# DoubleSwitch.net
KiCad netlist of a schematic drawn in EAGLE
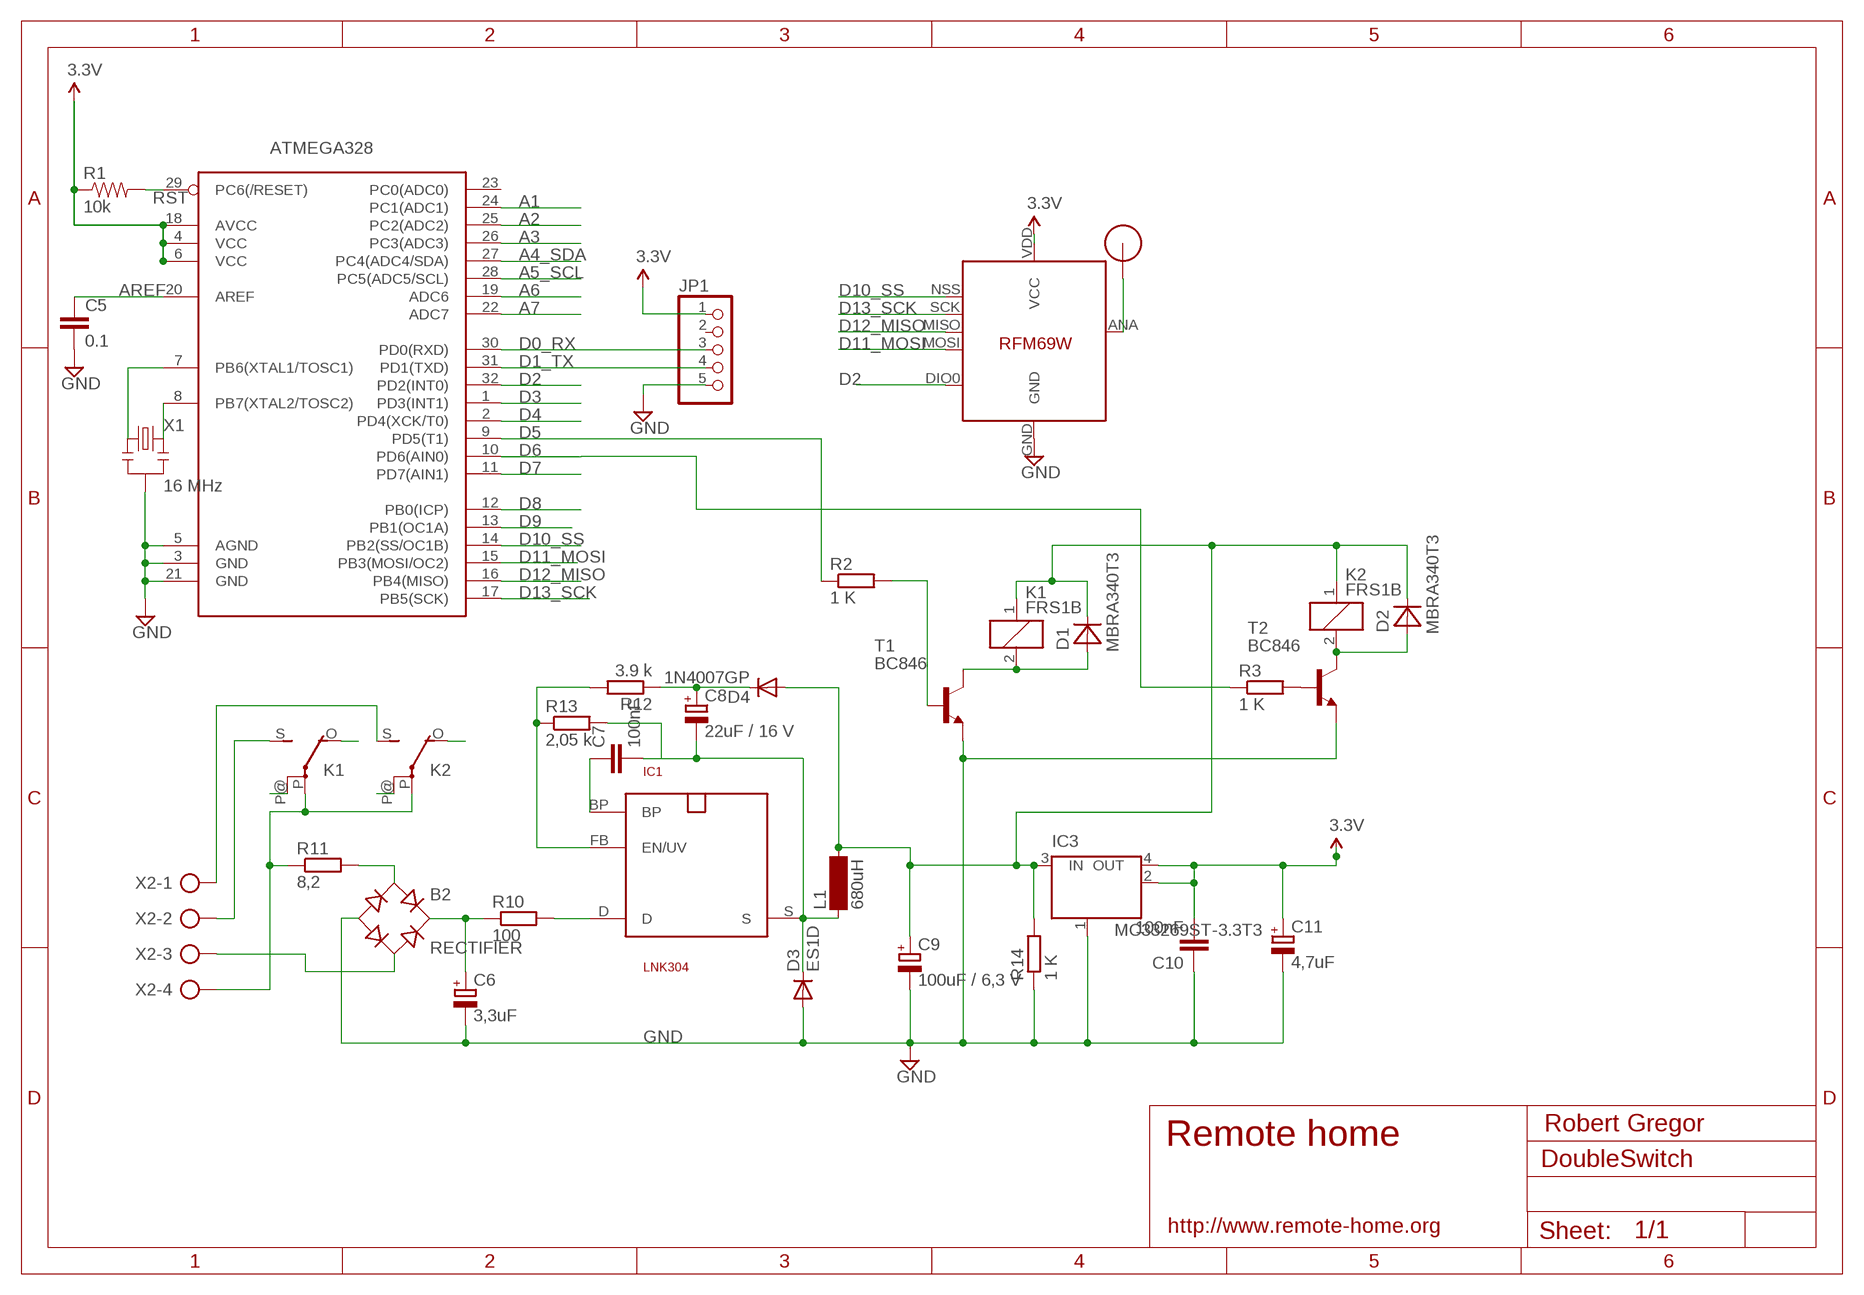
[diagram p0: schematic, sheet 1]

(export (version "E")
  (design (tool "Eeschema 10.0.6"))
  (components
    (comp (ref "ATMEGA328")
      (value "ATMega-328")
      (footprint "eagle-import:TQFP32-08")
      (libsource (lib "eagle-import") (part "ATMEGA168/328TQFP32"))
    )
    (comp (ref "B2")
      (value "RECTIFIER")
      (footprint "eagle-import:TO-269AA")
      (libsource (lib "eagle-import") (part "RECTIFIER-S40"))
    )
    (comp (ref "C5")
      (value "0.1")
      (footprint "eagle-import:0603-CAP")
      (libsource (lib "eagle-import") (part "CAP0603-CAP"))
    )
    (comp (ref "C6")
      (value "3,3uF")
      (footprint "eagle-import:E5-10,5")
      (libsource (lib "eagle-import") (part "CPOL-EUE5-10.5"))
    )
    (comp (ref "C7")
      (value "100nF")
      (footprint "eagle-import:C2012")
      (libsource (lib "eagle-import") (part "C-EUC2012"))
    )
    (comp (ref "C8")
      (value "22uF / 16 V")
      (footprint "eagle-import:SMC_C")
      (libsource (lib "eagle-import") (part "CPOL-EUSMCC"))
    )
    (comp (ref "C9")
      (value "100uF / 6,3 V")
      (footprint "eagle-import:E2,5-5")
      (libsource (lib "eagle-import") (part "CPOL-EUE2.5-5"))
    )
    (comp (ref "C10")
      (value "100nF")
      (footprint "eagle-import:C2012")
      (libsource (lib "eagle-import") (part "C-EUC2012"))
    )
    (comp (ref "C11")
      (value "4,7uF")
      (footprint "eagle-import:SMC_A")
      (libsource (lib "eagle-import") (part "CPOL-EUSMCA"))
    )
    (comp (ref "D1")
      (value "MBRA340T3")
      (footprint "eagle-import:SMA")
      (libsource (lib "eagle-import") (part "MBRA340T3"))
    )
    (comp (ref "D2")
      (value "MBRA340T3")
      (footprint "eagle-import:SMA")
      (libsource (lib "eagle-import") (part "MBRA340T3"))
    )
    (comp (ref "D3")
      (value "ES1D")
      (footprint "eagle-import:DO214AC")
      (libsource (lib "eagle-import") (part "DIODE-DO214AC"))
    )
    (comp (ref "D4")
      (value "1N4007GP")
      (footprint "eagle-import:DO214AA")
      (libsource (lib "eagle-import") (part "DIODE-DO214AA"))
    )
    (comp (ref "IC1")
      (value "LNK304")
      (footprint "eagle-import:SO-8C")
      (libsource (lib "eagle-import") (part "SO-8C"))
    )
    (comp (ref "IC3")
      (value "MC33269ST-3.3T3")
      (footprint "eagle-import:SOT223")
      (libsource (lib "eagle-import") (part "MC33269ST-3.3T3"))
    )
    (comp (ref "JP1")
      (value "PINHD-1X5")
      (footprint "eagle-import:1X05")
      (libsource (lib "eagle-import") (part "PINHD-1X5"))
    )
    (comp (ref "K1")
      (value "FRS1B")
      (footprint "eagle-import:FRS1B")
      (libsource (lib "eagle-import") (part "FRS1B"))
    )
    (comp (ref "K2")
      (value "FRS1B")
      (footprint "eagle-import:FRS1B")
      (libsource (lib "eagle-import") (part "FRS1B"))
    )
    (comp (ref "L1")
      (value "680uH")
      (footprint "eagle-import:BS11")
      (libsource (lib "eagle-import") (part "BS11"))
    )
    (comp (ref "R1")
      (value "10k")
      (footprint "eagle-import:0603-RES")
      (libsource (lib "eagle-import") (part "RESISTOR0603-RES"))
    )
    (comp (ref "R2")
      (value "1 K")
      (footprint "eagle-import:M2012")
      (libsource (lib "eagle-import") (part "R-EU_M2012"))
    )
    (comp (ref "R3")
      (value "1 K")
      (footprint "eagle-import:M2012")
      (libsource (lib "eagle-import") (part "R-EU_M2012"))
    )
    (comp (ref "R10")
      (value "100")
      (footprint "eagle-import:R2512W")
      (libsource (lib "eagle-import") (part "R-EU_R2512W"))
    )
    (comp (ref "R11")
      (value "8,2")
      (footprint "eagle-import:0411_12")
      (libsource (lib "eagle-import") (part "R-EU_0411/12"))
    )
    (comp (ref "R12")
      (value "3.9 k")
      (footprint "eagle-import:M2012")
      (libsource (lib "eagle-import") (part "R-EU_M2012"))
    )
    (comp (ref "R13")
      (value "2,05 k")
      (footprint "eagle-import:M2012")
      (libsource (lib "eagle-import") (part "R-EU_M2012"))
    )
    (comp (ref "R14")
      (value "1 K")
      (footprint "eagle-import:M2012")
      (libsource (lib "eagle-import") (part "R-EU_M2012"))
    )
    (comp (ref "T1")
      (value "BC846")
      (footprint "eagle-import:SOT23")
      (libsource (lib "eagle-import") (part "BC846"))
    )
    (comp (ref "T2")
      (value "BC846")
      (footprint "eagle-import:SOT23")
      (libsource (lib "eagle-import") (part "BC846"))
    )
    (comp (ref "U$1")
      (value "RFM12B_ANTENNA")
      (footprint "eagle-import:RFM12B-ANTENNA")
      (libsource (lib "eagle-import") (part "RFM12B_ANTENNA"))
    )
    (comp (ref "U$5")
      (value "RFM69")
      (footprint "eagle-import:RFM69W-MINPADS")
      (libsource (lib "eagle-import") (part "RFM69"))
    )
    (comp (ref "X1")
      (value "16 MHz")
      (footprint "eagle-import:RESONATOR-SMD")
      (libsource (lib "eagle-import") (part "RESONATORSMD"))
    )
    (comp (ref "X2")
      (value "AK500/4")
      (footprint "eagle-import:AK500_4")
      (libsource (lib "eagle-import") (part "AK500/4"))
    )
  )
  (nets
    (net (code "1") (name "/A1") (class "Default")
      (node (ref "ATMEGA328") (pin "24") (pinfunction "PC1(ADC1)_24") (pintype "bidirectional"))
    )
    (net (code "2") (name "/A2") (class "Default")
      (node (ref "ATMEGA328") (pin "25") (pinfunction "PC2(ADC2)_25") (pintype "bidirectional"))
    )
    (net (code "3") (name "/A3") (class "Default")
      (node (ref "ATMEGA328") (pin "26") (pinfunction "PC3(ADC3)_26") (pintype "bidirectional"))
    )
    (net (code "4") (name "/A4_SDA") (class "Default")
      (node (ref "ATMEGA328") (pin "27") (pinfunction "PC4(ADC4/SDA)_27") (pintype "bidirectional"))
    )
    (net (code "5") (name "/A5_SCL") (class "Default")
      (node (ref "ATMEGA328") (pin "28") (pinfunction "PC5(ADC5/SCL)_28") (pintype "bidirectional"))
    )
    (net (code "6") (name "/A6") (class "Default")
      (node (ref "ATMEGA328") (pin "19") (pinfunction "ADC6_19") (pintype "bidirectional"))
    )
    (net (code "7") (name "/A7") (class "Default")
      (node (ref "ATMEGA328") (pin "22") (pinfunction "ADC7_22") (pintype "bidirectional"))
    )
    (net (code "8") (name "/AREF") (class "Default")
      (node (ref "ATMEGA328") (pin "20") (pinfunction "AREF_20") (pintype "bidirectional"))
      (node (ref "C5") (pin "1") (pinfunction "1_1") (pintype "passive"))
    )
    (net (code "9") (name "/D0_RX") (class "Default")
      (node (ref "ATMEGA328") (pin "30") (pinfunction "PD0(RXD)_30") (pintype "bidirectional"))
      (node (ref "JP1") (pin "3") (pinfunction "3_3") (pintype "passive"))
    )
    (net (code "10") (name "/D1_TX") (class "Default")
      (node (ref "ATMEGA328") (pin "31") (pinfunction "PD1(TXD)_31") (pintype "bidirectional"))
      (node (ref "JP1") (pin "4") (pinfunction "4_4") (pintype "passive"))
    )
    (net (code "11") (name "/D2") (class "Default")
      (node (ref "ATMEGA328") (pin "32") (pinfunction "PD2(INT0)_32") (pintype "bidirectional"))
      (node (ref "U$5") (pin "DIO0") (pinfunction "DIO0_DIO0") (pintype "open_collector"))
    )
    (net (code "12") (name "/D3") (class "Default")
      (node (ref "ATMEGA328") (pin "1") (pinfunction "PD3(INT1)_1") (pintype "bidirectional"))
    )
    (net (code "13") (name "/D4") (class "Default")
      (node (ref "ATMEGA328") (pin "2") (pinfunction "PD4(XCK/T0)_2") (pintype "bidirectional"))
    )
    (net (code "14") (name "/D5") (class "Default")
      (node (ref "ATMEGA328") (pin "9") (pinfunction "PD5(T1)_9") (pintype "bidirectional"))
      (node (ref "R2") (pin "1") (pinfunction "1_1") (pintype "passive"))
    )
    (net (code "15") (name "/D6") (class "Default")
      (node (ref "ATMEGA328") (pin "10") (pinfunction "PD6(AIN0)_10") (pintype "bidirectional"))
      (node (ref "R3") (pin "1") (pinfunction "1_1") (pintype "passive"))
    )
    (net (code "16") (name "/D7") (class "Default")
      (node (ref "ATMEGA328") (pin "11") (pinfunction "PD7(AIN1)_11") (pintype "bidirectional"))
    )
    (net (code "17") (name "/D8") (class "Default")
      (node (ref "ATMEGA328") (pin "12") (pinfunction "PB0(ICP)_12") (pintype "bidirectional"))
    )
    (net (code "18") (name "/D9") (class "Default")
      (node (ref "ATMEGA328") (pin "13") (pinfunction "PB1(OC1A)_13") (pintype "bidirectional"))
    )
    (net (code "19") (name "/D10_SS") (class "Default")
      (node (ref "ATMEGA328") (pin "14") (pinfunction "PB2(SS/OC1B)_14") (pintype "bidirectional"))
      (node (ref "U$5") (pin "NSS") (pinfunction "SEL_NSS") (pintype "input"))
    )
    (net (code "20") (name "/D11_MOSI") (class "Default")
      (node (ref "ATMEGA328") (pin "15") (pinfunction "PB3(MOSI/OC2)_15") (pintype "bidirectional"))
      (node (ref "U$5") (pin "MOSI") (pinfunction "MOSI_MOSI") (pintype "output"))
    )
    (net (code "21") (name "/D12_MISO") (class "Default")
      (node (ref "ATMEGA328") (pin "16") (pinfunction "PB4(MISO)_16") (pintype "bidirectional"))
      (node (ref "U$5") (pin "MISO") (pinfunction "MISO_MISO") (pintype "input"))
    )
    (net (code "22") (name "/D13_SCK") (class "Default")
      (node (ref "ATMEGA328") (pin "17") (pinfunction "PB5(SCK)_17") (pintype "bidirectional"))
      (node (ref "U$5") (pin "SCK") (pinfunction "SCK_SCK") (pintype "input"))
    )
    (net (code "23") (name "/RST") (class "Default")
      (node (ref "ATMEGA328") (pin "29") (pinfunction "PC6(/RESET)_29") (pintype "bidirectional"))
      (node (ref "R1") (pin "2") (pinfunction "2_2") (pintype "passive"))
    )
    (net (code "24") (name "3.3V") (class "Default")
      (node (ref "ATMEGA328") (pin "18") (pinfunction "AVCC_18") (pintype "bidirectional"))
      (node (ref "ATMEGA328") (pin "4") (pinfunction "VCC_4") (pintype "bidirectional"))
      (node (ref "ATMEGA328") (pin "6") (pinfunction "VCC_6") (pintype "bidirectional"))
      (node (ref "C10") (pin "2") (pinfunction "2_2") (pintype "passive"))
      (node (ref "C11") (pin "+") (pinfunction "+_+") (pintype "passive"))
      (node (ref "IC3") (pin "2") (pinfunction "OUT_2") (pintype "passive"))
      (node (ref "IC3") (pin "4") (pinfunction "OUT_4") (pintype "passive"))
      (node (ref "JP1") (pin "1") (pinfunction "1_1") (pintype "passive"))
      (node (ref "R1") (pin "1") (pinfunction "1_1") (pintype "passive"))
      (node (ref "U$5") (pin "VDD") (pinfunction "VCC_VDD") (pintype "power_in"))
    )
    (net (code "25") (name "GND") (class "Default")
      (node (ref "ATMEGA328") (pin "21") (pinfunction "GND_21") (pintype "bidirectional"))
      (node (ref "ATMEGA328") (pin "3") (pinfunction "GND_3") (pintype "bidirectional"))
      (node (ref "ATMEGA328") (pin "5") (pinfunction "AGND_5") (pintype "bidirectional"))
      (node (ref "B2") (pin "-") (pinfunction "-_-") (pintype "passive"))
      (node (ref "C10") (pin "1") (pinfunction "1_1") (pintype "passive"))
      (node (ref "C11") (pin "-") (pinfunction "-_-") (pintype "passive"))
      (node (ref "C5") (pin "2") (pinfunction "2_2") (pintype "passive"))
      (node (ref "C6") (pin "-") (pinfunction "-_-") (pintype "passive"))
      (node (ref "C9") (pin "-") (pinfunction "-_-") (pintype "passive"))
      (node (ref "D3") (pin "A") (pinfunction "A_A") (pintype "passive"))
      (node (ref "IC3") (pin "1") (pinfunction "GND/ADJ_1") (pintype "input"))
      (node (ref "JP1") (pin "5") (pinfunction "5_5") (pintype "passive"))
      (node (ref "R14") (pin "1") (pinfunction "1_1") (pintype "passive"))
      (node (ref "T1") (pin "2") (pinfunction "E_2") (pintype "passive"))
      (node (ref "T2") (pin "2") (pinfunction "E_2") (pintype "passive"))
      (node (ref "U$5") (pin "GND") (pinfunction "GND_GND") (pintype "power_in"))
      (node (ref "X1") (pin "2") (pinfunction "2_2") (pintype "passive"))
    )
    (net (code "26") (name "Net-(ATMEGA328-PB6(XTAL1{slash}TOSC1))") (class "Default")
      (node (ref "ATMEGA328") (pin "7") (pinfunction "PB6(XTAL1/TOSC1)_7") (pintype "bidirectional"))
      (node (ref "X1") (pin "1") (pinfunction "1_1") (pintype "passive"))
    )
    (net (code "27") (name "Net-(ATMEGA328-PB7(XTAL2{slash}TOSC2))") (class "Default")
      (node (ref "ATMEGA328") (pin "8") (pinfunction "PB7(XTAL2/TOSC2)_8") (pintype "bidirectional"))
      (node (ref "X1") (pin "3") (pinfunction "3_3") (pintype "passive"))
    )
    (net (code "28") (name "Net-(B2-Pad+)") (class "Default")
      (node (ref "B2") (pin "+") (pinfunction "+_+") (pintype "passive"))
      (node (ref "C6") (pin "+") (pinfunction "+_+") (pintype "passive"))
      (node (ref "R10") (pin "1") (pinfunction "1_1") (pintype "passive"))
    )
    (net (code "29") (name "Net-(B2-PadAC1)") (class "Default")
      (node (ref "B2") (pin "AC1") (pinfunction "AC1_AC1") (pintype "passive"))
      (node (ref "R11") (pin "2") (pinfunction "2_2") (pintype "passive"))
    )
    (net (code "30") (name "Net-(C7-Pad1)") (class "Default")
      (node (ref "C7") (pin "1") (pinfunction "1_1") (pintype "passive"))
      (node (ref "IC1") (pin "BP") (pinfunction "BP_BP") (pintype "passive"))
    )
    (net (code "31") (name "Net-(C7-Pad2)") (class "Default")
      (node (ref "C7") (pin "2") (pinfunction "2_2") (pintype "passive"))
      (node (ref "C8") (pin "-") (pinfunction "-_-") (pintype "passive"))
      (node (ref "D3") (pin "C") (pinfunction "C_C") (pintype "passive"))
      (node (ref "IC1") (pin "S") (pinfunction "S_S") (pintype "power_in"))
      (node (ref "L1") (pin "1") (pinfunction "1_1") (pintype "passive"))
      (node (ref "R13") (pin "2") (pinfunction "2_2") (pintype "passive"))
    )
    (net (code "32") (name "Net-(C8-Pad+)") (class "Default")
      (node (ref "C8") (pin "+") (pinfunction "+_+") (pintype "passive"))
      (node (ref "D4") (pin "C") (pinfunction "C_C") (pintype "passive"))
      (node (ref "R12") (pin "1") (pinfunction "1_1") (pintype "passive"))
    )
    (net (code "33") (name "Net-(IC1-EN{slash}UV)") (class "Default")
      (node (ref "IC1") (pin "FB") (pinfunction "EN/UV_FB") (pintype "input"))
      (node (ref "R12") (pin "2") (pinfunction "2_2") (pintype "passive"))
      (node (ref "R13") (pin "1") (pinfunction "1_1") (pintype "passive"))
    )
    (net (code "34") (name "Net-(IC1-PadD)") (class "Default")
      (node (ref "IC1") (pin "D") (pinfunction "D_D") (pintype "open_collector"))
      (node (ref "R10") (pin "2") (pinfunction "2_2") (pintype "passive"))
    )
    (net (code "35") (name "Net-(IC3-IN)") (class "Default")
      (node (ref "C9") (pin "+") (pinfunction "+_+") (pintype "passive"))
      (node (ref "D1") (pin "C") (pinfunction "C_C") (pintype "passive"))
      (node (ref "D2") (pin "C") (pinfunction "C_C") (pintype "passive"))
      (node (ref "D4") (pin "A") (pinfunction "A_A") (pintype "passive"))
      (node (ref "IC3") (pin "3") (pinfunction "IN_3") (pintype "input"))
      (node (ref "K1") (pin "1") (pinfunction "1_1") (pintype "passive"))
      (node (ref "K2") (pin "1") (pinfunction "1_1") (pintype "passive"))
      (node (ref "L1") (pin "2") (pinfunction "2_2") (pintype "passive"))
      (node (ref "R14") (pin "2") (pinfunction "2_2") (pintype "passive"))
    )
    (net (code "36") (name "Net-(T1-B)") (class "Default")
      (node (ref "R2") (pin "2") (pinfunction "2_2") (pintype "passive"))
      (node (ref "T1") (pin "1") (pinfunction "B_1") (pintype "passive"))
    )
    (net (code "37") (name "Net-(T1-C)") (class "Default")
      (node (ref "D1") (pin "A") (pinfunction "A_A") (pintype "passive"))
      (node (ref "K1") (pin "2") (pinfunction "2_2") (pintype "passive"))
      (node (ref "T1") (pin "3") (pinfunction "C_3") (pintype "passive"))
    )
    (net (code "38") (name "Net-(T2-B)") (class "Default")
      (node (ref "R3") (pin "2") (pinfunction "2_2") (pintype "passive"))
      (node (ref "T2") (pin "1") (pinfunction "B_1") (pintype "passive"))
    )
    (net (code "39") (name "Net-(T2-C)") (class "Default")
      (node (ref "D2") (pin "A") (pinfunction "A_A") (pintype "passive"))
      (node (ref "K2") (pin "2") (pinfunction "2_2") (pintype "passive"))
      (node (ref "T2") (pin "3") (pinfunction "C_3") (pintype "passive"))
    )
    (net (code "40") (name "Net-(U$1-1)") (class "Default")
      (node (ref "U$1") (pin "P$1") (pinfunction "1_P$1") (pintype "bidirectional"))
      (node (ref "U$5") (pin "ANA") (pinfunction "ANT_ANA") (pintype "passive"))
    )
    (net (code "41") (name "Net-(X2A-KL)") (class "Default")
      (node (ref "K2") (pin "S") (pinfunction "S_S") (pintype "passive"))
      (node (ref "X2") (pin "1") (pinfunction "KL_1") (pintype "passive"))
    )
    (net (code "42") (name "Net-(X2B-KL)") (class "Default")
      (node (ref "K1") (pin "S") (pinfunction "S_S") (pintype "passive"))
      (node (ref "X2") (pin "2") (pinfunction "KL_2") (pintype "passive"))
    )
    (net (code "43") (name "Net-(X2C-KL)") (class "Default")
      (node (ref "B2") (pin "AC2") (pinfunction "AC2_AC2") (pintype "passive"))
      (node (ref "X2") (pin "3") (pinfunction "KL_3") (pintype "passive"))
    )
    (net (code "44") (name "Net-(X2D-KL)") (class "Default")
      (node (ref "K1") (pin "P") (pinfunction "P_P") (pintype "passive"))
      (node (ref "K2") (pin "P") (pinfunction "P_P") (pintype "passive"))
      (node (ref "R11") (pin "1") (pinfunction "1_1") (pintype "passive"))
      (node (ref "X2") (pin "4") (pinfunction "KL_4") (pintype "passive"))
    )
    (net (code "45") (name "unconnected-(ATMEGA328-PC0(ADC0)-Pad23)") (class "Default")
      (node (ref "ATMEGA328") (pin "23") (pinfunction "PC0(ADC0)_23") (pintype "bidirectional"))
    )
    (net (code "46") (name "unconnected-(JP1-Pad2)") (class "Default")
      (node (ref "JP1") (pin "2") (pinfunction "2_2") (pintype "passive"))
    )
    (net (code "47") (name "unconnected-(K1-PadO)") (class "Default")
      (node (ref "K1") (pin "O") (pinfunction "O_O") (pintype "passive"))
    )
    (net (code "48") (name "unconnected-(K1B-P-PadP@)") (class "Default")
      (node (ref "K1") (pin "P@") (pinfunction "P_P@") (pintype "passive"))
    )
    (net (code "49") (name "unconnected-(K2-PadO)") (class "Default")
      (node (ref "K2") (pin "O") (pinfunction "O_O") (pintype "passive"))
    )
    (net (code "50") (name "unconnected-(K2B-P-PadP@)") (class "Default")
      (node (ref "K2") (pin "P@") (pinfunction "P_P@") (pintype "passive"))
    )
  )
)
